# Power.net
KiCad netlist of a schematic drawn in Altium Designer
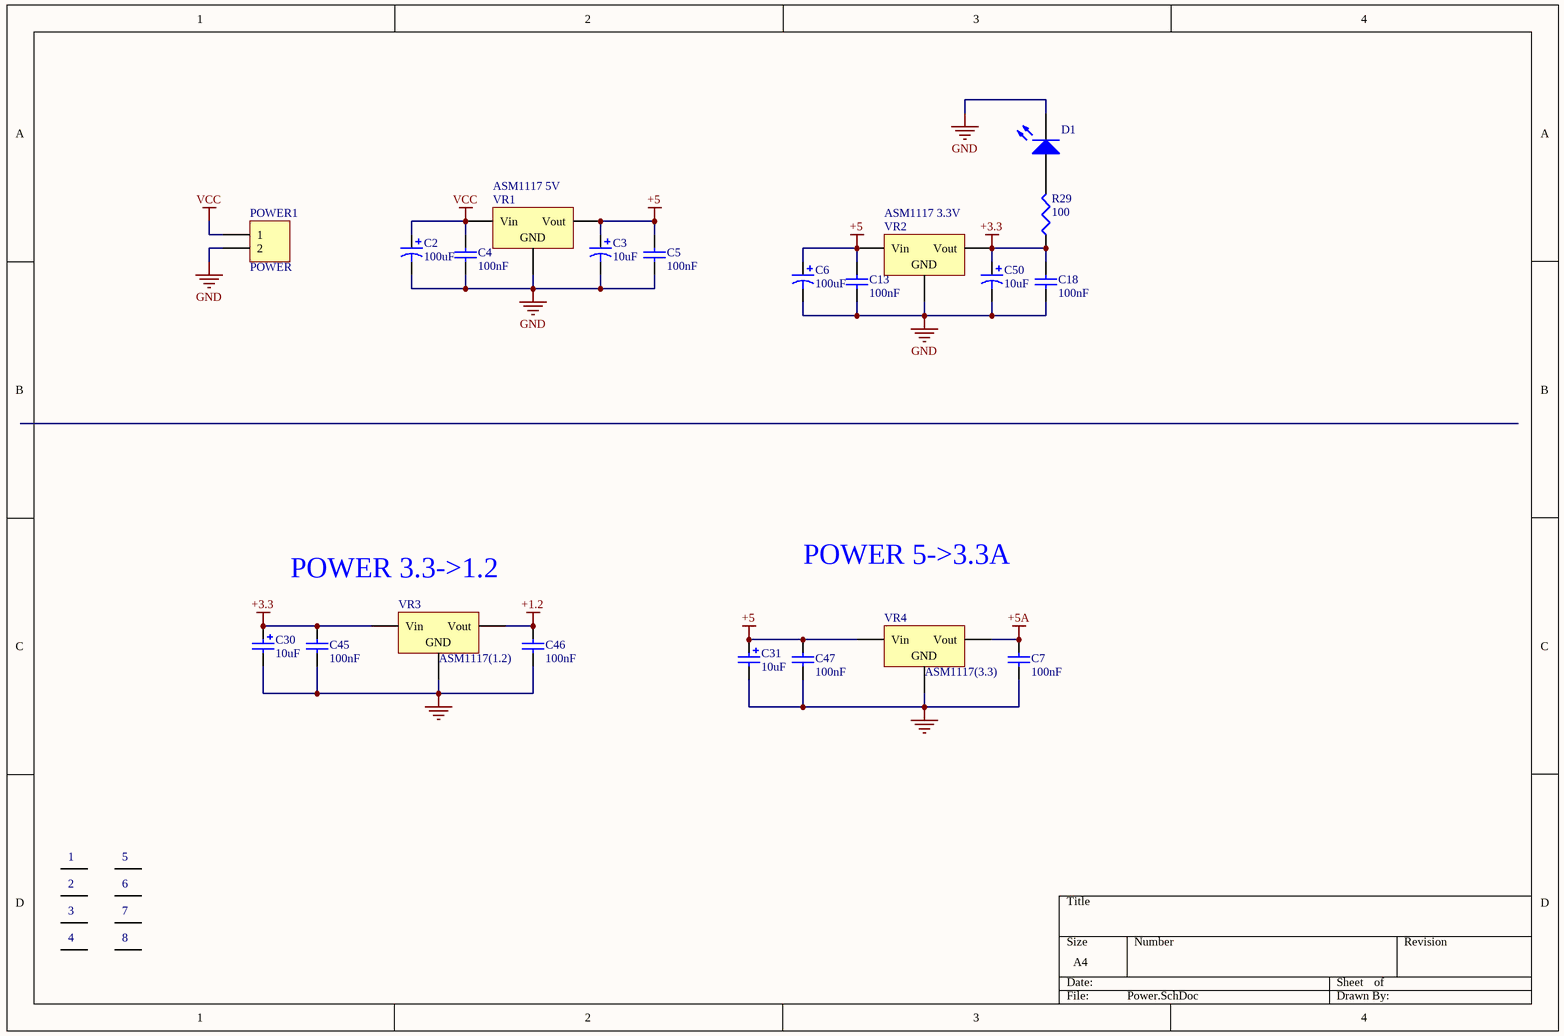
[diagram p0: Power.SchDoc]

(export (version "E")
  (design (tool "Eeschema 10.0.6"))
  (components
    (comp (ref "1") (value "~") (footprint "pad") (libsource (lib "bobsch") (part "PAD")))
    (comp (ref "2") (value "~") (footprint "pad") (libsource (lib "bobsch") (part "PAD")))
    (comp (ref "3") (value "~") (footprint "pad") (libsource (lib "bobsch") (part "PAD")))
    (comp (ref "4") (value "~") (footprint "pad") (libsource (lib "bobsch") (part "PAD")))
    (comp (ref "5") (value "~") (footprint "pad") (libsource (lib "bobsch") (part "PAD")))
    (comp (ref "6") (value "~") (footprint "pad") (libsource (lib "bobsch") (part "PAD")))
    (comp (ref "7") (value "~") (footprint "pad") (libsource (lib "bobsch") (part "PAD")))
    (comp (ref "8") (value "~") (footprint "pad") (libsource (lib "bobsch") (part "PAD")))
    (comp (ref "C2")
      (value "100uF")
      (footprint "CAP470")
      (description "Polarized Capacitor (Radial)")
      (fields (field (name "Comment") "100uf") (field (name "PUBLISHER") "Altium Limited"))
      (libsource (lib "") (part "Cap Pol1_1"))
    )
    (comp (ref "C3")
      (value "10uF")
      (footprint "CAP1016")
      (description "Polarized Capacitor (Radial)")
      (fields (field (name "Comment") "10uf") (field (name "PUBLISHER") "Altium Limited"))
      (libsource (lib "") (part "Cap Pol1_1"))
    )
    (comp (ref "C4")
      (value "100nF")
      (footprint "1206")
      (description "Capacitor (Semiconductor SIM Model)")
      (fields (field (name "PUBLISHER") "Altium Limited"))
      (libsource (lib "Miscellaneous Devices") (part "Cap Semi"))
    )
    (comp (ref "C5")
      (value "100nF")
      (footprint "1206")
      (description "Capacitor (Semiconductor SIM Model)")
      (fields (field (name "PUBLISHER") "Altium Limited"))
      (libsource (lib "Miscellaneous Devices") (part "Cap Semi"))
    )
    (comp (ref "C6")
      (value "100uF")
      (footprint "CAP470")
      (description "Polarized Capacitor (Radial)")
      (fields (field (name "Comment") "100uf") (field (name "PUBLISHER") "Altium Limited"))
      (libsource (lib "") (part "Cap Pol1_1"))
    )
    (comp (ref "C7")
      (value "100nF")
      (footprint "1206")
      (description "Capacitor")
      (fields (field (name "PUBLISHER") "Altium Limited"))
      (libsource (lib "Miscellaneous Devices") (part "Cap"))
    )
    (comp (ref "C13")
      (value "100nF")
      (footprint "1206")
      (description "Capacitor (Semiconductor SIM Model)")
      (fields (field (name "PUBLISHER") "Altium Limited"))
      (libsource (lib "Miscellaneous Devices") (part "Cap Semi"))
    )
    (comp (ref "C18")
      (value "100nF")
      (footprint "1206")
      (description "Capacitor (Semiconductor SIM Model)")
      (fields (field (name "PUBLISHER") "Altium Limited"))
      (libsource (lib "Miscellaneous Devices") (part "Cap Semi"))
    )
    (comp (ref "C30")
      (value "10uF")
      (footprint "CAP1016")
      (description "Polarized Capacitor (Radial)")
      (fields (field (name "PUBLISHER") "Altium Limited"))
      (libsource (lib "Miscellaneous Devices") (part "Cap Pol1"))
    )
    (comp (ref "C31")
      (value "10uF")
      (footprint "CAP1016")
      (description "Polarized Capacitor (Radial)")
      (fields (field (name "PUBLISHER") "Altium Limited"))
      (libsource (lib "Miscellaneous Devices") (part "Cap Pol1"))
    )
    (comp (ref "C45")
      (value "100nF")
      (footprint "1206")
      (description "Capacitor")
      (fields (field (name "PUBLISHER") "Altium Limited"))
      (libsource (lib "Miscellaneous Devices") (part "Cap"))
    )
    (comp (ref "C46")
      (value "100nF")
      (footprint "1206")
      (description "Capacitor")
      (fields (field (name "PUBLISHER") "Altium Limited"))
      (libsource (lib "Miscellaneous Devices") (part "Cap"))
    )
    (comp (ref "C47")
      (value "100nF")
      (footprint "1206")
      (description "Capacitor")
      (fields (field (name "PUBLISHER") "Altium Limited"))
      (libsource (lib "Miscellaneous Devices") (part "Cap"))
    )
    (comp (ref "C50")
      (value "10uF")
      (footprint "CAP1016")
      (description "Polarized Capacitor (Radial)")
      (fields (field (name "Comment") "10uf") (field (name "PUBLISHER") "Altium Limited"))
      (libsource (lib "") (part "Cap Pol1_1"))
    )
    (comp (ref "D1")
      (value "LED0")
      (footprint "LED-0805")
      (description "Typical INFRARED GaAs LED")
      (fields (field (name "PUBLISHER") "Altium Limited"))
      (libsource (lib "Miscellaneous Devices") (part "LED0"))
    )
    (comp (ref "POWER1")
      (value "POWER")
      (footprint "power jack")
      (description "Header, 2-Pin, Right Angle")
      (fields (field (name "PUBLISHER") "Altium Limited"))
      (libsource (lib "Miscellaneous Connectors") (part "Header 2H"))
    )
    (comp (ref "R29")
      (value "100")
      (footprint "1206")
      (description "Resistor")
      (fields (field (name "PUBLISHER") "Altium Limited"))
      (libsource (lib "Miscellaneous Devices") (part "Res3"))
    )
    (comp (ref "VR1")
      (value "ASM1117 5V")
      (footprint "AMS117")
      (description "Voltage Regulator")
      (fields (field (name "PUBLISHER") "Altium Limited"))
      (libsource (lib "Miscellaneous Devices") (part "Volt Reg_1"))
    )
    (comp (ref "VR2")
      (value "ASM1117 3.3V")
      (footprint "AMS117")
      (description "Voltage Regulator")
      (fields (field (name "PUBLISHER") "Altium Limited"))
      (libsource (lib "Miscellaneous Devices") (part "Volt Reg_1"))
    )
    (comp (ref "VR3")
      (value "ASM1117(1.2)")
      (footprint "AMS117")
      (description "Voltage Regulator")
      (fields (field (name "PUBLISHER") "Altium Limited"))
      (libsource (lib "Miscellaneous Devices") (part "Volt Reg_1"))
    )
    (comp (ref "VR4")
      (value "ASM1117(3.3)")
      (footprint "AMS117")
      (description "Voltage Regulator")
      (fields (field (name "PUBLISHER") "Altium Limited"))
      (libsource (lib "Miscellaneous Devices") (part "Volt Reg_1"))
    )
  )
  (nets
    (net (code "1") (name "+1.2") (class "Default")
      (node (ref "C46") (pin "1") (pinfunction "1_1") (pintype "passive"))
      (node (ref "VR3") (pin "4") (pinfunction "Vout_4") (pintype "passive"))
    )
    (net (code "2") (name "+3.3") (class "Default")
      (node (ref "C18") (pin "1") (pinfunction "1_1") (pintype "passive"))
      (node (ref "C30") (pin "1") (pinfunction "1_1") (pintype "passive"))
      (node (ref "C45") (pin "1") (pinfunction "1_1") (pintype "passive"))
      (node (ref "C50") (pin "1") (pinfunction "1_1") (pintype "passive"))
      (node (ref "R29") (pin "1") (pinfunction "1_1") (pintype "passive"))
      (node (ref "VR2") (pin "4") (pinfunction "Vout_4") (pintype "passive"))
      (node (ref "VR3") (pin "3") (pinfunction "Vin_3") (pintype "passive"))
    )
    (net (code "3") (name "+5") (class "Default")
      (node (ref "C13") (pin "1") (pinfunction "1_1") (pintype "passive"))
      (node (ref "C3") (pin "1") (pinfunction "1_1") (pintype "passive"))
      (node (ref "C31") (pin "1") (pinfunction "1_1") (pintype "passive"))
      (node (ref "C47") (pin "1") (pinfunction "1_1") (pintype "passive"))
      (node (ref "C5") (pin "1") (pinfunction "1_1") (pintype "passive"))
      (node (ref "C6") (pin "1") (pinfunction "1_1") (pintype "passive"))
      (node (ref "VR1") (pin "4") (pinfunction "Vout_4") (pintype "passive"))
      (node (ref "VR2") (pin "3") (pinfunction "Vin_3") (pintype "passive"))
      (node (ref "VR4") (pin "3") (pinfunction "Vin_3") (pintype "passive"))
    )
    (net (code "4") (name "+5A") (class "Default")
      (node (ref "C7") (pin "1") (pinfunction "1_1") (pintype "passive"))
      (node (ref "VR4") (pin "4") (pinfunction "Vout_4") (pintype "passive"))
    )
    (net (code "5") (name "GND") (class "Default")
      (node (ref "C13") (pin "2") (pinfunction "2_2") (pintype "passive"))
      (node (ref "C18") (pin "2") (pinfunction "2_2") (pintype "passive"))
      (node (ref "C2") (pin "2") (pinfunction "2_2") (pintype "passive"))
      (node (ref "C3") (pin "2") (pinfunction "2_2") (pintype "passive"))
      (node (ref "C30") (pin "2") (pinfunction "2_2") (pintype "passive"))
      (node (ref "C31") (pin "2") (pinfunction "2_2") (pintype "passive"))
      (node (ref "C4") (pin "2") (pinfunction "2_2") (pintype "passive"))
      (node (ref "C45") (pin "2") (pinfunction "2_2") (pintype "passive"))
      (node (ref "C46") (pin "2") (pinfunction "2_2") (pintype "passive"))
      (node (ref "C47") (pin "2") (pinfunction "2_2") (pintype "passive"))
      (node (ref "C5") (pin "2") (pinfunction "2_2") (pintype "passive"))
      (node (ref "C50") (pin "2") (pinfunction "2_2") (pintype "passive"))
      (node (ref "C6") (pin "2") (pinfunction "2_2") (pintype "passive"))
      (node (ref "C7") (pin "2") (pinfunction "2_2") (pintype "passive"))
      (node (ref "D1") (pin "2") (pinfunction "K_2") (pintype "passive"))
      (node (ref "POWER1") (pin "2") (pinfunction "2_2") (pintype "passive"))
      (node (ref "VR1") (pin "1") (pinfunction "GND_1") (pintype "passive"))
      (node (ref "VR2") (pin "1") (pinfunction "GND_1") (pintype "passive"))
      (node (ref "VR3") (pin "1") (pinfunction "GND_1") (pintype "passive"))
      (node (ref "VR4") (pin "1") (pinfunction "GND_1") (pintype "passive"))
    )
    (net (code "6") (name "Net-(D1-A)") (class "Default")
      (node (ref "D1") (pin "1") (pinfunction "A_1") (pintype "passive"))
      (node (ref "R29") (pin "2") (pinfunction "2_2") (pintype "passive"))
    )
    (net (code "7") (name "VCC") (class "Default")
      (node (ref "C2") (pin "1") (pinfunction "1_1") (pintype "passive"))
      (node (ref "C4") (pin "1") (pinfunction "1_1") (pintype "passive"))
      (node (ref "POWER1") (pin "1") (pinfunction "1_1") (pintype "passive"))
      (node (ref "VR1") (pin "3") (pinfunction "Vin_3") (pintype "passive"))
    )
    (net (code "8") (name "unconnected-(1-Pad1)") (class "Default")
      (node (ref "1") (pin "1") (pinfunction "1_1") (pintype "passive"))
    )
    (net (code "9") (name "unconnected-(2-Pad1)") (class "Default")
      (node (ref "2") (pin "1") (pinfunction "1_1") (pintype "passive"))
    )
    (net (code "10") (name "unconnected-(3-Pad1)") (class "Default")
      (node (ref "3") (pin "1") (pinfunction "1_1") (pintype "passive"))
    )
    (net (code "11") (name "unconnected-(4-Pad1)") (class "Default")
      (node (ref "4") (pin "1") (pinfunction "1_1") (pintype "passive"))
    )
    (net (code "12") (name "unconnected-(5-Pad1)") (class "Default")
      (node (ref "5") (pin "1") (pinfunction "1_1") (pintype "passive"))
    )
    (net (code "13") (name "unconnected-(6-Pad1)") (class "Default")
      (node (ref "6") (pin "1") (pinfunction "1_1") (pintype "passive"))
    )
    (net (code "14") (name "unconnected-(7-Pad1)") (class "Default")
      (node (ref "7") (pin "1") (pinfunction "1_1") (pintype "passive"))
    )
    (net (code "15") (name "unconnected-(8-Pad1)") (class "Default")
      (node (ref "8") (pin "1") (pinfunction "1_1") (pintype "passive"))
    )
  )
)
